# 9volt_rail.net
KiCad netlist of a schematic drawn in EAGLE
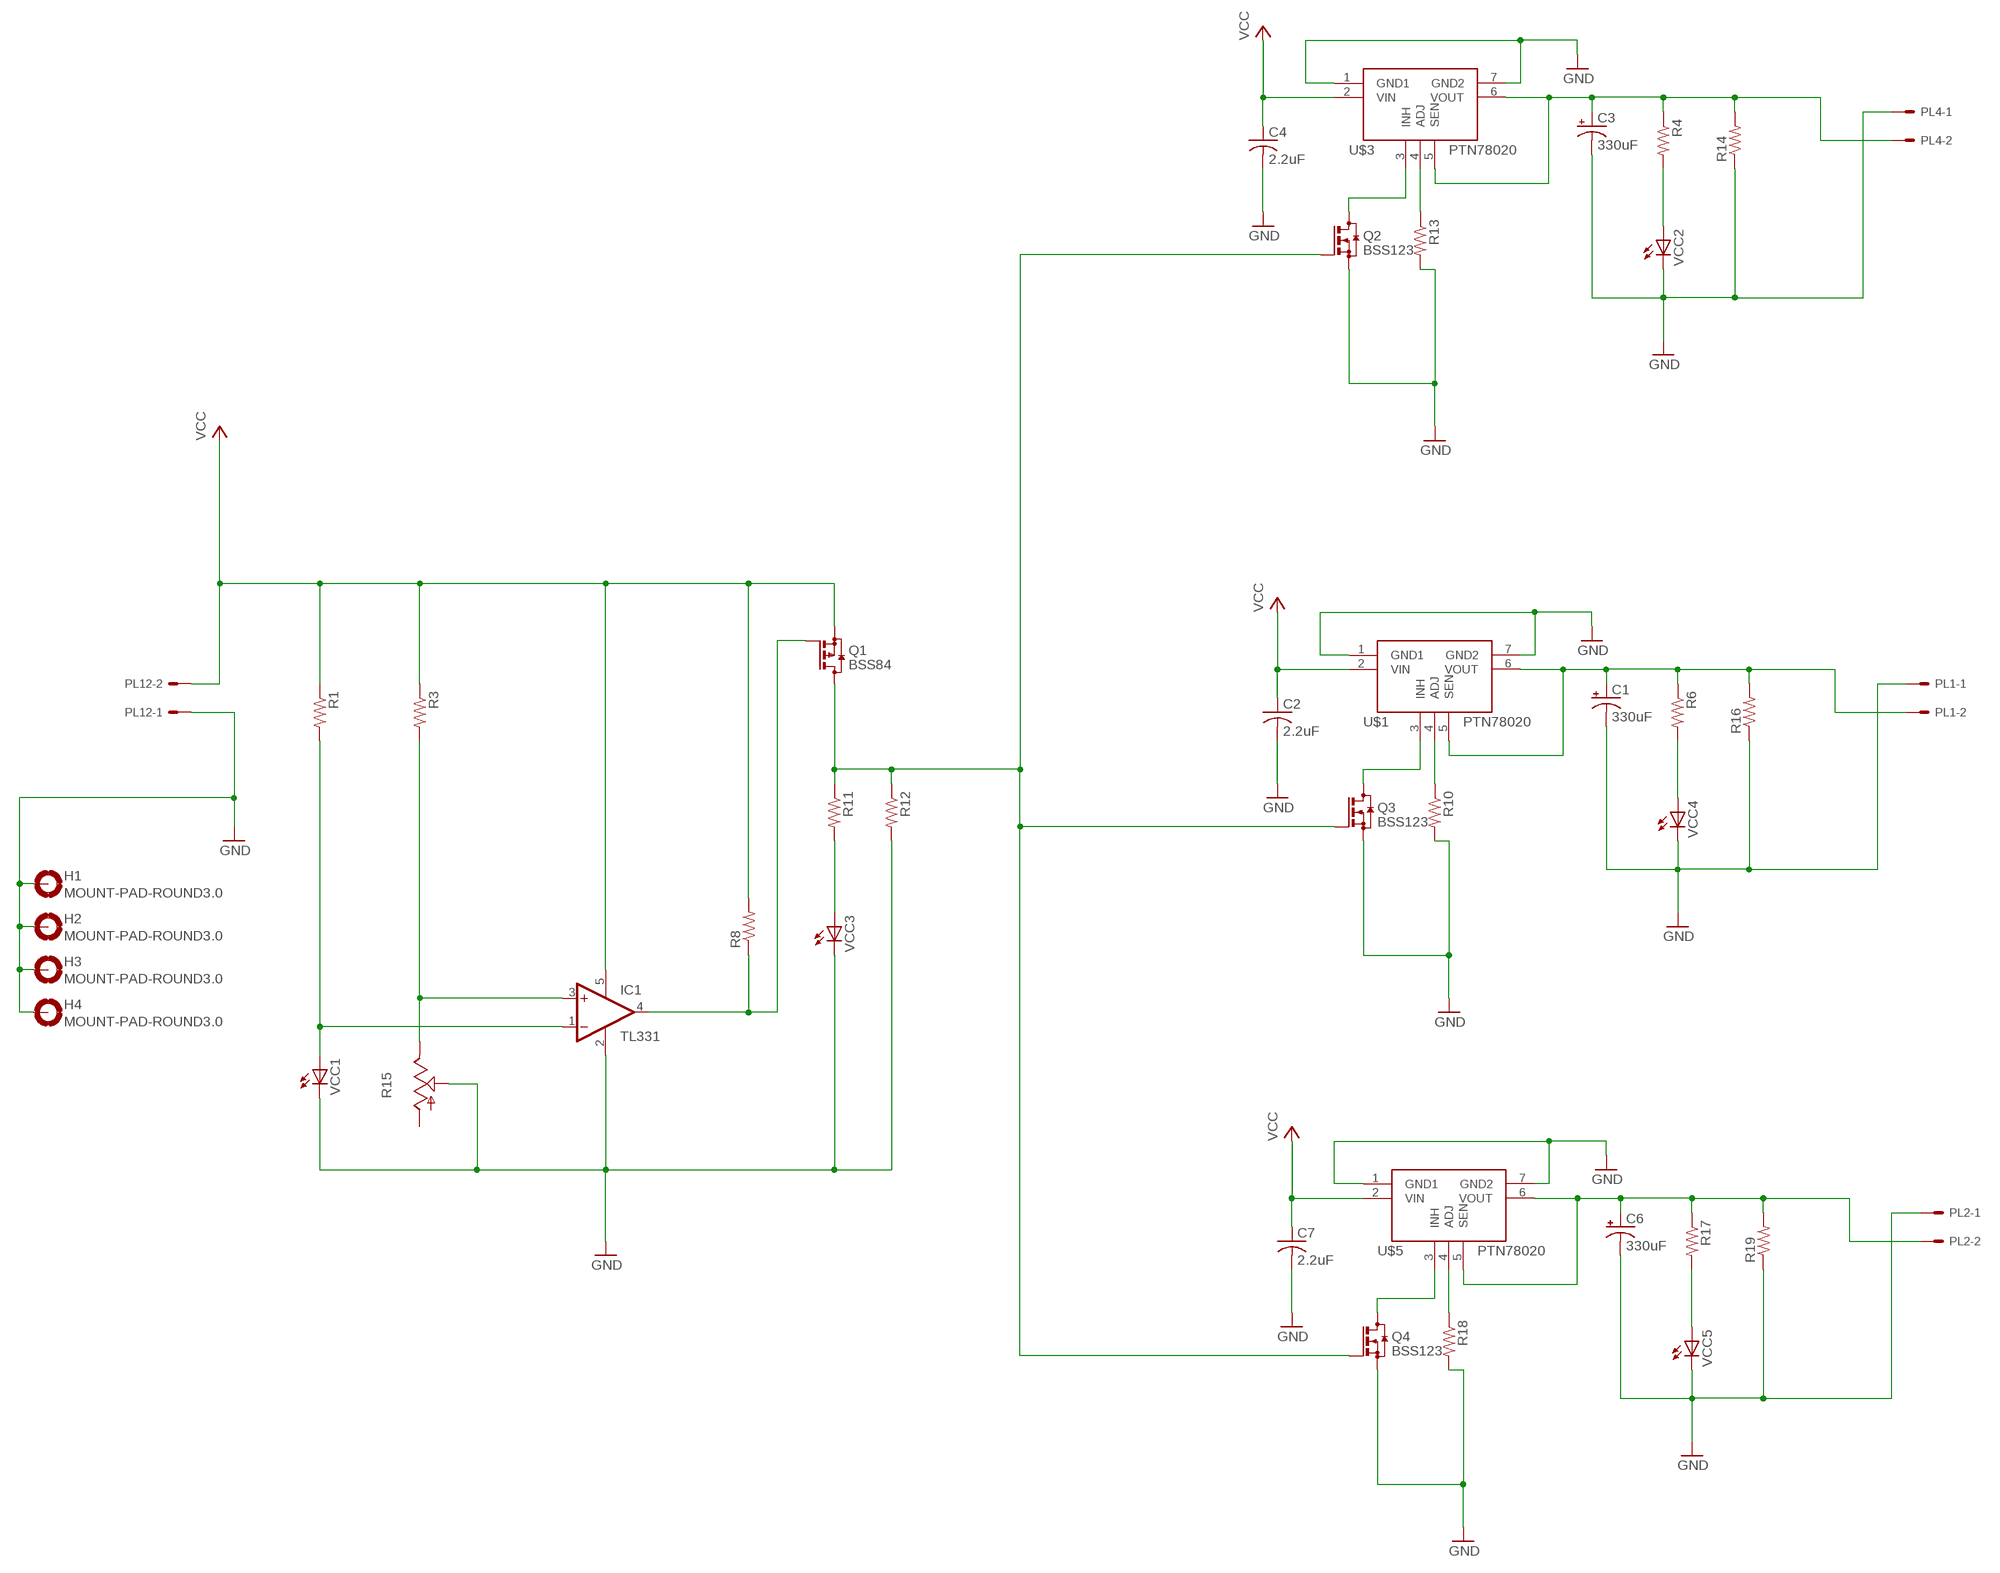
[diagram p0: schematic, sheet 1]

(export (version "E")
  (design (tool "Eeschema 10.0.6"))
  (components
    (comp (ref "C1")
      (value "330uF")
      (footprint "eagle-import:E5-10,5")
      (libsource (lib "eagle-import") (part "CPOL-USE5-10.5"))
    )
    (comp (ref "C2")
      (value "2.2uF")
      (footprint "eagle-import:C0805")
      (libsource (lib "eagle-import") (part "C-USC0805"))
    )
    (comp (ref "C3")
      (value "330uF")
      (footprint "eagle-import:E5-10,5")
      (libsource (lib "eagle-import") (part "CPOL-USE5-10.5"))
    )
    (comp (ref "C4")
      (value "2.2uF")
      (footprint "eagle-import:C0805")
      (libsource (lib "eagle-import") (part "C-USC0805"))
    )
    (comp (ref "C6")
      (value "330uF")
      (footprint "eagle-import:E5-10,5")
      (libsource (lib "eagle-import") (part "CPOL-USE5-10.5"))
    )
    (comp (ref "C7")
      (value "2.2uF")
      (footprint "eagle-import:C0805")
      (libsource (lib "eagle-import") (part "C-USC0805"))
    )
    (comp (ref "H1")
      (value "MOUNT-PAD-ROUND3.0")
      (footprint "eagle-import:3,0-PAD")
      (libsource (lib "eagle-import") (part "MOUNT-PAD-ROUND3.0"))
    )
    (comp (ref "H2")
      (value "MOUNT-PAD-ROUND3.0")
      (footprint "eagle-import:3,0-PAD")
      (libsource (lib "eagle-import") (part "MOUNT-PAD-ROUND3.0"))
    )
    (comp (ref "H3")
      (value "MOUNT-PAD-ROUND3.0")
      (footprint "eagle-import:3,0-PAD")
      (libsource (lib "eagle-import") (part "MOUNT-PAD-ROUND3.0"))
    )
    (comp (ref "H4")
      (value "MOUNT-PAD-ROUND3.0")
      (footprint "eagle-import:3,0-PAD")
      (libsource (lib "eagle-import") (part "MOUNT-PAD-ROUND3.0"))
    )
    (comp (ref "IC1")
      (value "TL331")
      (footprint "eagle-import:DBV-R-PDSO-G5")
      (libsource (lib "eagle-import") (part "TL331"))
    )
    (comp (ref "PL1")
      (value "555X-2H")
      (footprint "eagle-import:5569-2")
      (libsource (lib "eagle-import") (part "555X-2H"))
    )
    (comp (ref "PL2")
      (value "555X-2H")
      (footprint "eagle-import:5569-2")
      (libsource (lib "eagle-import") (part "555X-2H"))
    )
    (comp (ref "PL4")
      (value "555X-2H")
      (footprint "eagle-import:5569-2")
      (libsource (lib "eagle-import") (part "555X-2H"))
    )
    (comp (ref "PL12")
      (value "555X-2H")
      (footprint "eagle-import:5569-2")
      (libsource (lib "eagle-import") (part "555X-2H"))
    )
    (comp (ref "Q1")
      (value "BSS84")
      (footprint "eagle-import:SOT23")
      (libsource (lib "eagle-import") (part "BSS84"))
    )
    (comp (ref "Q2")
      (value "BSS123")
      (footprint "eagle-import:SOT23")
      (libsource (lib "eagle-import") (part "BSS123"))
    )
    (comp (ref "Q3")
      (value "BSS123")
      (footprint "eagle-import:SOT23")
      (libsource (lib "eagle-import") (part "BSS123"))
    )
    (comp (ref "Q4")
      (value "BSS123")
      (footprint "eagle-import:SOT23")
      (libsource (lib "eagle-import") (part "BSS123"))
    )
    (comp (ref "R1")
      (value "R-US_M0805")
      (footprint "eagle-import:M0805")
      (libsource (lib "eagle-import") (part "R-US_M0805"))
    )
    (comp (ref "R3")
      (value "R-US_M0805")
      (footprint "eagle-import:M0805")
      (libsource (lib "eagle-import") (part "R-US_M0805"))
    )
    (comp (ref "R4")
      (value "R-US_M0805")
      (footprint "eagle-import:M0805")
      (libsource (lib "eagle-import") (part "R-US_M0805"))
    )
    (comp (ref "R6")
      (value "R-US_M0805")
      (footprint "eagle-import:M0805")
      (libsource (lib "eagle-import") (part "R-US_M0805"))
    )
    (comp (ref "R8")
      (value "R-US_M0805")
      (footprint "eagle-import:M0805")
      (libsource (lib "eagle-import") (part "R-US_M0805"))
    )
    (comp (ref "R10")
      (value "R-US_M0805")
      (footprint "eagle-import:M0805")
      (libsource (lib "eagle-import") (part "R-US_M0805"))
    )
    (comp (ref "R11")
      (value "R-US_M0805")
      (footprint "eagle-import:M0805")
      (libsource (lib "eagle-import") (part "R-US_M0805"))
    )
    (comp (ref "R12")
      (value "R-US_M0805")
      (footprint "eagle-import:M0805")
      (libsource (lib "eagle-import") (part "R-US_M0805"))
    )
    (comp (ref "R13")
      (value "R-US_M0805")
      (footprint "eagle-import:M0805")
      (libsource (lib "eagle-import") (part "R-US_M0805"))
    )
    (comp (ref "R14")
      (value "R-US_0617/17")
      (footprint "eagle-import:0617_17")
      (libsource (lib "eagle-import") (part "resistor_R-US_0617/17"))
    )
    (comp (ref "R15")
      (value "TRIM_US-S63P")
      (footprint "eagle-import:S63P")
      (libsource (lib "eagle-import") (part "TRIM_US-S63P"))
    )
    (comp (ref "R16")
      (value "R-US_0617/17")
      (footprint "eagle-import:0617_17")
      (libsource (lib "eagle-import") (part "resistor_R-US_0617/17"))
    )
    (comp (ref "R17")
      (value "R-US_M0805")
      (footprint "eagle-import:M0805")
      (libsource (lib "eagle-import") (part "R-US_M0805"))
    )
    (comp (ref "R18")
      (value "R-US_M0805")
      (footprint "eagle-import:M0805")
      (libsource (lib "eagle-import") (part "R-US_M0805"))
    )
    (comp (ref "R19")
      (value "R-US_0617/17")
      (footprint "eagle-import:0617_17")
      (libsource (lib "eagle-import") (part "resistor_R-US_0617/17"))
    )
    (comp (ref "U$1")
      (value "PTH78020-SMD")
      (footprint "eagle-import:PTN78020-SND")
      (libsource (lib "eagle-import") (part "PTH78020-SMD"))
    )
    (comp (ref "U$3")
      (value "PTH78020-SMD")
      (footprint "eagle-import:PTN78020-SND")
      (libsource (lib "eagle-import") (part "PTH78020-SMD"))
    )
    (comp (ref "U$5")
      (value "PTH78020-SMD")
      (footprint "eagle-import:PTN78020-SND")
      (libsource (lib "eagle-import") (part "PTH78020-SMD"))
    )
    (comp (ref "VCC1")
      (value "LED5MM")
      (footprint "eagle-import:LED5MM")
      (libsource (lib "eagle-import") (part "LED5MM"))
    )
    (comp (ref "VCC2")
      (value "LED5MM")
      (footprint "eagle-import:LED5MM")
      (libsource (lib "eagle-import") (part "LED5MM"))
    )
    (comp (ref "VCC3")
      (value "LED5MM")
      (footprint "eagle-import:LED5MM")
      (libsource (lib "eagle-import") (part "LED5MM"))
    )
    (comp (ref "VCC4")
      (value "LED5MM")
      (footprint "eagle-import:LED5MM")
      (libsource (lib "eagle-import") (part "LED5MM"))
    )
    (comp (ref "VCC5")
      (value "LED5MM")
      (footprint "eagle-import:LED5MM")
      (libsource (lib "eagle-import") (part "LED5MM"))
    )
  )
  (nets
    (net (code "1") (name "GND") (class "Default")
      (node (ref "C1") (pin "-") (pinfunction "-_-") (pintype "passive"))
      (node (ref "C2") (pin "2") (pinfunction "2_2") (pintype "passive"))
      (node (ref "C3") (pin "-") (pinfunction "-_-") (pintype "passive"))
      (node (ref "C4") (pin "2") (pinfunction "2_2") (pintype "passive"))
      (node (ref "C6") (pin "-") (pinfunction "-_-") (pintype "passive"))
      (node (ref "C7") (pin "2") (pinfunction "2_2") (pintype "passive"))
      (node (ref "H1") (pin "B3,0") (pinfunction "MOUNT_B3,0") (pintype "passive"))
      (node (ref "H2") (pin "B3,0") (pinfunction "MOUNT_B3,0") (pintype "passive"))
      (node (ref "H3") (pin "B3,0") (pinfunction "MOUNT_B3,0") (pintype "passive"))
      (node (ref "H4") (pin "B3,0") (pinfunction "MOUNT_B3,0") (pintype "passive"))
      (node (ref "IC1") (pin "2") (pinfunction "GND_2") (pintype "power_in"))
      (node (ref "PL1") (pin "1") (pinfunction "S_1") (pintype "passive"))
      (node (ref "PL12") (pin "1") (pinfunction "S_1") (pintype "passive"))
      (node (ref "PL2") (pin "1") (pinfunction "S_1") (pintype "passive"))
      (node (ref "PL4") (pin "1") (pinfunction "S_1") (pintype "passive"))
      (node (ref "Q2") (pin "2") (pinfunction "S_2") (pintype "passive"))
      (node (ref "Q3") (pin "2") (pinfunction "S_2") (pintype "passive"))
      (node (ref "Q4") (pin "2") (pinfunction "S_2") (pintype "passive"))
      (node (ref "R10") (pin "2") (pinfunction "2_2") (pintype "passive"))
      (node (ref "R12") (pin "2") (pinfunction "2_2") (pintype "passive"))
      (node (ref "R13") (pin "2") (pinfunction "2_2") (pintype "passive"))
      (node (ref "R14") (pin "1") (pinfunction "1_1") (pintype "passive"))
      (node (ref "R15") (pin "S") (pinfunction "S_S") (pintype "passive"))
      (node (ref "R16") (pin "1") (pinfunction "1_1") (pintype "passive"))
      (node (ref "R18") (pin "2") (pinfunction "2_2") (pintype "passive"))
      (node (ref "R19") (pin "1") (pinfunction "1_1") (pintype "passive"))
      (node (ref "U$1") (pin "1") (pinfunction "GND1_1") (pintype "bidirectional"))
      (node (ref "U$1") (pin "7") (pinfunction "GND2_7") (pintype "bidirectional"))
      (node (ref "U$3") (pin "1") (pinfunction "GND1_1") (pintype "bidirectional"))
      (node (ref "U$3") (pin "7") (pinfunction "GND2_7") (pintype "bidirectional"))
      (node (ref "U$5") (pin "1") (pinfunction "GND1_1") (pintype "bidirectional"))
      (node (ref "U$5") (pin "7") (pinfunction "GND2_7") (pintype "bidirectional"))
      (node (ref "VCC1") (pin "K") (pinfunction "C_K") (pintype "passive"))
      (node (ref "VCC2") (pin "K") (pinfunction "C_K") (pintype "passive"))
      (node (ref "VCC3") (pin "K") (pinfunction "C_K") (pintype "passive"))
      (node (ref "VCC4") (pin "K") (pinfunction "C_K") (pintype "passive"))
      (node (ref "VCC5") (pin "K") (pinfunction "C_K") (pintype "passive"))
    )
    (net (code "2") (name "Net-(IC1-+IN)") (class "Default")
      (node (ref "IC1") (pin "3") (pinfunction "+IN_3") (pintype "input"))
      (node (ref "R15") (pin "E") (pinfunction "E_E") (pintype "passive"))
      (node (ref "R3") (pin "2") (pinfunction "2_2") (pintype "passive"))
    )
    (net (code "3") (name "Net-(IC1--IN)") (class "Default")
      (node (ref "IC1") (pin "1") (pinfunction "-IN_1") (pintype "input"))
      (node (ref "R1") (pin "2") (pinfunction "2_2") (pintype "passive"))
      (node (ref "VCC1") (pin "A") (pinfunction "A_A") (pintype "passive"))
    )
    (net (code "4") (name "Net-(IC1-OUT)") (class "Default")
      (node (ref "IC1") (pin "4") (pinfunction "OUT_4") (pintype "output"))
      (node (ref "Q1") (pin "1") (pinfunction "G_1") (pintype "passive"))
      (node (ref "R8") (pin "1") (pinfunction "1_1") (pintype "passive"))
    )
    (net (code "5") (name "Net-(PL1B-S)") (class "Default")
      (node (ref "C1") (pin "+") (pinfunction "+_+") (pintype "passive"))
      (node (ref "PL1") (pin "2") (pinfunction "S_2") (pintype "passive"))
      (node (ref "R16") (pin "2") (pinfunction "2_2") (pintype "passive"))
      (node (ref "R6") (pin "1") (pinfunction "1_1") (pintype "passive"))
      (node (ref "U$1") (pin "5") (pinfunction "SEN_5") (pintype "bidirectional"))
      (node (ref "U$1") (pin "6") (pinfunction "VOUT_6") (pintype "bidirectional"))
    )
    (net (code "6") (name "Net-(PL2B-S)") (class "Default")
      (node (ref "C6") (pin "+") (pinfunction "+_+") (pintype "passive"))
      (node (ref "PL2") (pin "2") (pinfunction "S_2") (pintype "passive"))
      (node (ref "R17") (pin "1") (pinfunction "1_1") (pintype "passive"))
      (node (ref "R19") (pin "2") (pinfunction "2_2") (pintype "passive"))
      (node (ref "U$5") (pin "5") (pinfunction "SEN_5") (pintype "bidirectional"))
      (node (ref "U$5") (pin "6") (pinfunction "VOUT_6") (pintype "bidirectional"))
    )
    (net (code "7") (name "Net-(PL4B-S)") (class "Default")
      (node (ref "C3") (pin "+") (pinfunction "+_+") (pintype "passive"))
      (node (ref "PL4") (pin "2") (pinfunction "S_2") (pintype "passive"))
      (node (ref "R14") (pin "2") (pinfunction "2_2") (pintype "passive"))
      (node (ref "R4") (pin "1") (pinfunction "1_1") (pintype "passive"))
      (node (ref "U$3") (pin "5") (pinfunction "SEN_5") (pintype "bidirectional"))
      (node (ref "U$3") (pin "6") (pinfunction "VOUT_6") (pintype "bidirectional"))
    )
    (net (code "8") (name "Net-(Q1-D)") (class "Default")
      (node (ref "Q1") (pin "3") (pinfunction "D_3") (pintype "passive"))
      (node (ref "Q2") (pin "1") (pinfunction "G_1") (pintype "passive"))
      (node (ref "Q3") (pin "1") (pinfunction "G_1") (pintype "passive"))
      (node (ref "Q4") (pin "1") (pinfunction "G_1") (pintype "passive"))
      (node (ref "R11") (pin "1") (pinfunction "1_1") (pintype "passive"))
      (node (ref "R12") (pin "1") (pinfunction "1_1") (pintype "passive"))
    )
    (net (code "9") (name "Net-(Q2-D)") (class "Default")
      (node (ref "Q2") (pin "3") (pinfunction "D_3") (pintype "passive"))
      (node (ref "U$3") (pin "3") (pinfunction "INH_3") (pintype "bidirectional"))
    )
    (net (code "10") (name "Net-(Q3-D)") (class "Default")
      (node (ref "Q3") (pin "3") (pinfunction "D_3") (pintype "passive"))
      (node (ref "U$1") (pin "3") (pinfunction "INH_3") (pintype "bidirectional"))
    )
    (net (code "11") (name "Net-(Q4-D)") (class "Default")
      (node (ref "Q4") (pin "3") (pinfunction "D_3") (pintype "passive"))
      (node (ref "U$5") (pin "3") (pinfunction "INH_3") (pintype "bidirectional"))
    )
    (net (code "12") (name "Net-(R4-Pad2)") (class "Default")
      (node (ref "R4") (pin "2") (pinfunction "2_2") (pintype "passive"))
      (node (ref "VCC2") (pin "A") (pinfunction "A_A") (pintype "passive"))
    )
    (net (code "13") (name "Net-(R6-Pad2)") (class "Default")
      (node (ref "R6") (pin "2") (pinfunction "2_2") (pintype "passive"))
      (node (ref "VCC4") (pin "A") (pinfunction "A_A") (pintype "passive"))
    )
    (net (code "14") (name "Net-(R11-Pad2)") (class "Default")
      (node (ref "R11") (pin "2") (pinfunction "2_2") (pintype "passive"))
      (node (ref "VCC3") (pin "A") (pinfunction "A_A") (pintype "passive"))
    )
    (net (code "15") (name "Net-(R17-Pad2)") (class "Default")
      (node (ref "R17") (pin "2") (pinfunction "2_2") (pintype "passive"))
      (node (ref "VCC5") (pin "A") (pinfunction "A_A") (pintype "passive"))
    )
    (net (code "16") (name "Net-(U$1-ADJ)") (class "Default")
      (node (ref "R10") (pin "1") (pinfunction "1_1") (pintype "passive"))
      (node (ref "U$1") (pin "4") (pinfunction "ADJ_4") (pintype "bidirectional"))
    )
    (net (code "17") (name "Net-(U$3-ADJ)") (class "Default")
      (node (ref "R13") (pin "1") (pinfunction "1_1") (pintype "passive"))
      (node (ref "U$3") (pin "4") (pinfunction "ADJ_4") (pintype "bidirectional"))
    )
    (net (code "18") (name "Net-(U$5-ADJ)") (class "Default")
      (node (ref "R18") (pin "1") (pinfunction "1_1") (pintype "passive"))
      (node (ref "U$5") (pin "4") (pinfunction "ADJ_4") (pintype "bidirectional"))
    )
    (net (code "19") (name "VCC") (class "Default")
      (node (ref "C2") (pin "1") (pinfunction "1_1") (pintype "passive"))
      (node (ref "C4") (pin "1") (pinfunction "1_1") (pintype "passive"))
      (node (ref "C7") (pin "1") (pinfunction "1_1") (pintype "passive"))
      (node (ref "IC1") (pin "5") (pinfunction "V+_5") (pintype "power_in"))
      (node (ref "PL12") (pin "2") (pinfunction "S_2") (pintype "passive"))
      (node (ref "Q1") (pin "2") (pinfunction "S_2") (pintype "passive"))
      (node (ref "R1") (pin "1") (pinfunction "1_1") (pintype "passive"))
      (node (ref "R3") (pin "1") (pinfunction "1_1") (pintype "passive"))
      (node (ref "R8") (pin "2") (pinfunction "2_2") (pintype "passive"))
      (node (ref "U$1") (pin "2") (pinfunction "VIN_2") (pintype "bidirectional"))
      (node (ref "U$3") (pin "2") (pinfunction "VIN_2") (pintype "bidirectional"))
      (node (ref "U$5") (pin "2") (pinfunction "VIN_2") (pintype "bidirectional"))
    )
    (net (code "20") (name "unconnected-(R15-PadA)") (class "Default")
      (node (ref "R15") (pin "A") (pinfunction "A_A") (pintype "passive"))
    )
  )
)
